# microSD_Connector.net
KiCad netlist of a schematic drawn in EAGLE
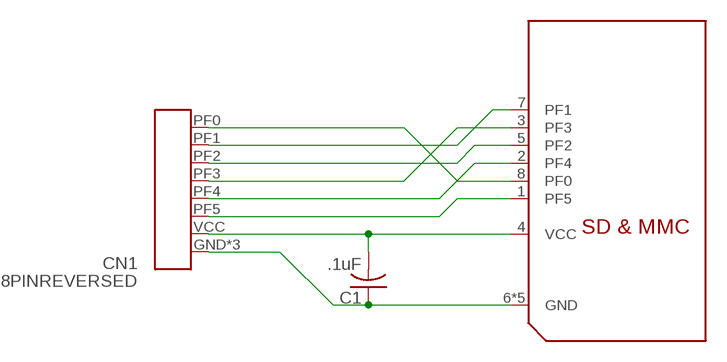
[diagram p0: schematic, sheet 1]

(export (version "E")
  (design (tool "Eeschema 10.0.6"))
  (components
    (comp (ref "C1")
      (value ".1uF")
      (footprint "eagle-import:C0805K")
      (libsource (lib "eagle-import") (part "C-USC0805K"))
    )
    (comp (ref "CN1")
      (value "8PINREVERSED")
      (footprint "eagle-import:SFV8R-3STBE1HLF-REVERSED")
      (libsource (lib "eagle-import") (part "8PINREVERSED"))
    )
    (comp (ref "U$1")
      (value "MICROSD")
      (footprint "eagle-import:MICROSD")
      (libsource (lib "eagle-import") (part "MICROSD"))
    )
  )
  (nets
    (net (code "1") (name "Net-(C1-Pad1)") (class "Default")
      (node (ref "C1") (pin "1") (pinfunction "1_1") (pintype "passive"))
      (node (ref "CN1") (pin "GND") (pinfunction "GND_GND") (pintype "bidirectional"))
      (node (ref "CN1") (pin "GNDP1") (pinfunction "GND_GNDP1") (pintype "bidirectional"))
      (node (ref "CN1") (pin "GNDP2") (pinfunction "GND_GNDP2") (pintype "bidirectional"))
      (node (ref "U$1") (pin "6") (pinfunction "GND_6") (pintype "power_in"))
      (node (ref "U$1") (pin "CD1") (pinfunction "GND_CD1") (pintype "power_in"))
      (node (ref "U$1") (pin "CD2") (pinfunction "GND_CD2") (pintype "power_in"))
      (node (ref "U$1") (pin "MT1") (pinfunction "GND_MT1") (pintype "power_in"))
      (node (ref "U$1") (pin "MT2") (pinfunction "GND_MT2") (pintype "power_in"))
    )
    (net (code "2") (name "Net-(U$1-PF0)") (class "Default")
      (node (ref "CN1") (pin "PF0") (pinfunction "PF0_PF0") (pintype "bidirectional"))
      (node (ref "U$1") (pin "8") (pinfunction "PF0_8") (pintype "bidirectional"))
    )
    (net (code "3") (name "Net-(U$1-PF1)") (class "Default")
      (node (ref "CN1") (pin "PF1") (pinfunction "PF1_PF1") (pintype "bidirectional"))
      (node (ref "U$1") (pin "7") (pinfunction "PF1_7") (pintype "output"))
    )
    (net (code "4") (name "Net-(U$1-PF2)") (class "Default")
      (node (ref "CN1") (pin "PF2") (pinfunction "PF2_PF2") (pintype "bidirectional"))
      (node (ref "U$1") (pin "5") (pinfunction "PF2_5") (pintype "input"))
    )
    (net (code "5") (name "Net-(U$1-PF3)") (class "Default")
      (node (ref "CN1") (pin "PF3") (pinfunction "PF3_PF3") (pintype "bidirectional"))
      (node (ref "U$1") (pin "3") (pinfunction "PF3_3") (pintype "input"))
    )
    (net (code "6") (name "Net-(U$1-PF4)") (class "Default")
      (node (ref "CN1") (pin "PF4") (pinfunction "PF4_PF4") (pintype "bidirectional"))
      (node (ref "U$1") (pin "2") (pinfunction "PF4_2") (pintype "input"))
    )
    (net (code "7") (name "Net-(U$1-PF5)") (class "Default")
      (node (ref "CN1") (pin "PF5") (pinfunction "PF5_PF5") (pintype "bidirectional"))
      (node (ref "U$1") (pin "1") (pinfunction "PF5_1") (pintype "bidirectional"))
    )
    (net (code "8") (name "Net-(U$1-VCC)") (class "Default")
      (node (ref "C1") (pin "2") (pinfunction "2_2") (pintype "passive"))
      (node (ref "CN1") (pin "VCC") (pinfunction "VCC_VCC") (pintype "bidirectional"))
      (node (ref "U$1") (pin "4") (pinfunction "VCC_4") (pintype "power_in"))
    )
  )
)
